# MHI-AC-Ctrl_v2_2.net
KiCad netlist of a schematic drawn in EAGLE
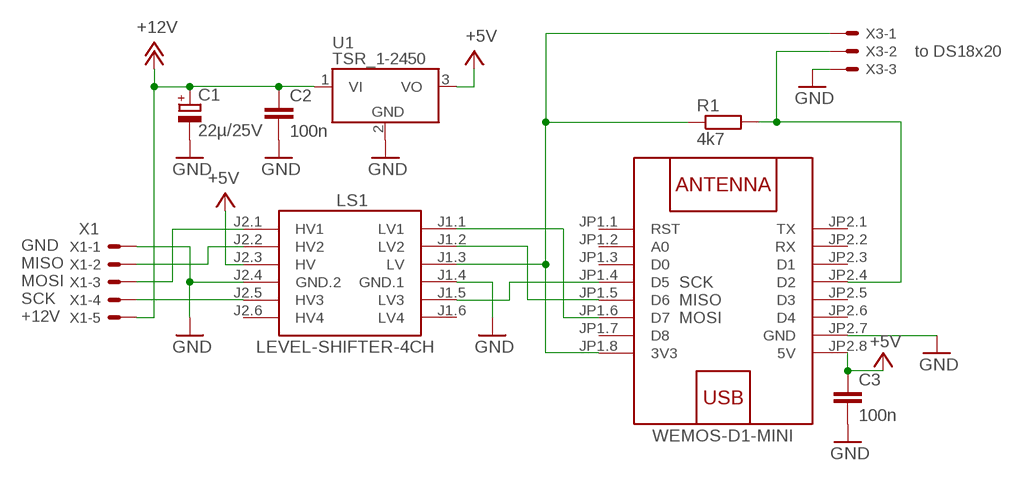
[diagram p0: schematic, sheet 1]

(export (version "E")
  (design (tool "Eeschema 10.0.6"))
  (components
    (comp (ref "C1")
      (value "22µ/25V")
      (footprint "eagle-import:E15-5")
      (libsource (lib "eagle-import") (part "CPOL-EUE15-5AXIAL"))
    )
    (comp (ref "C2")
      (value "100n")
      (footprint "eagle-import:C025-024X044")
      (libsource (lib "eagle-import") (part "C-EU025-024X044"))
    )
    (comp (ref "C3")
      (value "100n")
      (footprint "eagle-import:C025-024X044")
      (libsource (lib "eagle-import") (part "C-EU025-024X044"))
    )
    (comp (ref "LS1")
      (value "LEVEL-SHIFTER-4CH")
      (footprint "eagle-import:LEVEL-SHIFTER-4CH")
      (libsource (lib "eagle-import") (part "LEVEL-SHIFTER-4CH"))
    )
    (comp (ref "R1")
      (value "4k7")
      (footprint "eagle-import:0207_10")
      (libsource (lib "eagle-import") (part "R-EU_0207/10"))
    )
    (comp (ref "U$1")
      (value "WEMOS-D1-MINI")
      (footprint "eagle-import:WEMOS-D1-MINI")
      (libsource (lib "eagle-import") (part "WEMOS-D1-MINI"))
    )
    (comp (ref "U1")
      (value "TSR_1-2450")
      (footprint "eagle-import:TSR-1")
      (libsource (lib "eagle-import") (part "TSR_1-24_"))
    )
    (comp (ref "X1")
      (value "JST 03JQ-BT")
      (footprint "eagle-import:JST-XH-05-PACKAGE-LONG-PAD")
      (libsource (lib "eagle-import") (part "JST-JQ-05-LONG-PAD"))
    )
    (comp (ref "X3")
      (value "JST-XH-03-PIN")
      (footprint "eagle-import:JST-XH-03-ST90-PACKAGE-LONG-PAD")
      (libsource (lib "eagle-import") (part "JST-XH-03-PIN"))
    )
  )
  (nets
    (net (code "1") (name "+5V") (class "Default")
      (node (ref "C3") (pin "1") (pinfunction "1_1") (pintype "passive"))
      (node (ref "LS1") (pin "J2.3") (pinfunction "HV_J2.3") (pintype "power_in"))
      (node (ref "U$1") (pin "JP2.8") (pinfunction "5V_JP2.8") (pintype "power_in"))
      (node (ref "U1") (pin "3") (pinfunction "VO_3") (pintype "power_in"))
    )
    (net (code "2") (name "+12V") (class "Default")
      (node (ref "C1") (pin "+") (pinfunction "+_+") (pintype "passive"))
      (node (ref "C2") (pin "1") (pinfunction "1_1") (pintype "passive"))
      (node (ref "U1") (pin "1") (pinfunction "VI_1") (pintype "power_in"))
      (node (ref "X1") (pin "5") (pinfunction "S_5") (pintype "passive"))
    )
    (net (code "3") (name "/MISO") (class "Default")
      (node (ref "LS1") (pin "J2.2") (pinfunction "HV2_J2.2") (pintype "bidirectional"))
      (node (ref "X1") (pin "2") (pinfunction "S_2") (pintype "passive"))
    )
    (net (code "4") (name "/MOSI") (class "Default")
      (node (ref "LS1") (pin "J2.1") (pinfunction "HV1_J2.1") (pintype "bidirectional"))
      (node (ref "X1") (pin "3") (pinfunction "S_3") (pintype "passive"))
    )
    (net (code "5") (name "/SCK") (class "Default")
      (node (ref "LS1") (pin "J2.5") (pinfunction "HV3_J2.5") (pintype "bidirectional"))
      (node (ref "X1") (pin "4") (pinfunction "S_4") (pintype "passive"))
    )
    (net (code "6") (name "GND") (class "Default")
      (node (ref "C1") (pin "-") (pinfunction "-_-") (pintype "passive"))
      (node (ref "C2") (pin "2") (pinfunction "2_2") (pintype "passive"))
      (node (ref "C3") (pin "2") (pinfunction "2_2") (pintype "passive"))
      (node (ref "LS1") (pin "J1.4") (pinfunction "GND.1_J1.4") (pintype "power_in"))
      (node (ref "LS1") (pin "J2.4") (pinfunction "GND.2_J2.4") (pintype "power_in"))
      (node (ref "U$1") (pin "JP2.7") (pinfunction "GND_JP2.7") (pintype "power_in"))
      (node (ref "U1") (pin "2") (pinfunction "GND_2") (pintype "power_in"))
      (node (ref "X1") (pin "1") (pinfunction "S_1") (pintype "passive"))
      (node (ref "X3") (pin "3") (pinfunction "S_3") (pintype "passive"))
    )
    (net (code "7") (name "Net-(LS1-LV)") (class "Default")
      (node (ref "LS1") (pin "J1.3") (pinfunction "LV_J1.3") (pintype "power_in"))
      (node (ref "R1") (pin "1") (pinfunction "1_1") (pintype "passive"))
      (node (ref "U$1") (pin "JP1.8") (pinfunction "3V3_JP1.8") (pintype "power_in"))
      (node (ref "X3") (pin "1") (pinfunction "S_1") (pintype "passive"))
    )
    (net (code "8") (name "Net-(LS1-LV1)") (class "Default")
      (node (ref "LS1") (pin "J1.1") (pinfunction "LV1_J1.1") (pintype "bidirectional"))
      (node (ref "U$1") (pin "JP1.6") (pinfunction "D7_JP1.6") (pintype "bidirectional"))
    )
    (net (code "9") (name "Net-(LS1-LV2)") (class "Default")
      (node (ref "LS1") (pin "J1.2") (pinfunction "LV2_J1.2") (pintype "bidirectional"))
      (node (ref "U$1") (pin "JP1.5") (pinfunction "D6_JP1.5") (pintype "bidirectional"))
    )
    (net (code "10") (name "Net-(LS1-LV3)") (class "Default")
      (node (ref "LS1") (pin "J1.5") (pinfunction "LV3_J1.5") (pintype "bidirectional"))
      (node (ref "U$1") (pin "JP1.4") (pinfunction "D5_JP1.4") (pintype "bidirectional"))
    )
    (net (code "11") (name "Net-(U$1-D2)") (class "Default")
      (node (ref "R1") (pin "2") (pinfunction "2_2") (pintype "passive"))
      (node (ref "U$1") (pin "JP2.4") (pinfunction "D2_JP2.4") (pintype "bidirectional"))
      (node (ref "X3") (pin "2") (pinfunction "S_2") (pintype "passive"))
    )
    (net (code "12") (name "unconnected-(LS1-HV4-PadJ2.6)") (class "Default")
      (node (ref "LS1") (pin "J2.6") (pinfunction "HV4_J2.6") (pintype "bidirectional"))
    )
    (net (code "13") (name "unconnected-(LS1-LV4-PadJ1.6)") (class "Default")
      (node (ref "LS1") (pin "J1.6") (pinfunction "LV4_J1.6") (pintype "bidirectional"))
    )
    (net (code "14") (name "unconnected-(U$1-A0-PadJP1.2)") (class "Default")
      (node (ref "U$1") (pin "JP1.2") (pinfunction "A0_JP1.2") (pintype "bidirectional"))
    )
    (net (code "15") (name "unconnected-(U$1-D0-PadJP1.3)") (class "Default")
      (node (ref "U$1") (pin "JP1.3") (pinfunction "D0_JP1.3") (pintype "bidirectional"))
    )
    (net (code "16") (name "unconnected-(U$1-D1-PadJP2.3)") (class "Default")
      (node (ref "U$1") (pin "JP2.3") (pinfunction "D1_JP2.3") (pintype "bidirectional"))
    )
    (net (code "17") (name "unconnected-(U$1-D3-PadJP2.5)") (class "Default")
      (node (ref "U$1") (pin "JP2.5") (pinfunction "D3_JP2.5") (pintype "bidirectional"))
    )
    (net (code "18") (name "unconnected-(U$1-D4-PadJP2.6)") (class "Default")
      (node (ref "U$1") (pin "JP2.6") (pinfunction "D4_JP2.6") (pintype "bidirectional"))
    )
    (net (code "19") (name "unconnected-(U$1-D8-PadJP1.7)") (class "Default")
      (node (ref "U$1") (pin "JP1.7") (pinfunction "D8_JP1.7") (pintype "bidirectional"))
    )
    (net (code "20") (name "unconnected-(U$1-RST-PadJP1.1)") (class "Default")
      (node (ref "U$1") (pin "JP1.1") (pinfunction "RST_JP1.1") (pintype "bidirectional"))
    )
    (net (code "21") (name "unconnected-(U$1-RX-PadJP2.2)") (class "Default")
      (node (ref "U$1") (pin "JP2.2") (pinfunction "RX_JP2.2") (pintype "bidirectional"))
    )
    (net (code "22") (name "unconnected-(U$1-TX-PadJP2.1)") (class "Default")
      (node (ref "U$1") (pin "JP2.1") (pinfunction "TX_JP2.1") (pintype "bidirectional"))
    )
  )
)
